# WS2811S.net
KiCad netlist of a schematic drawn in Altium Designer
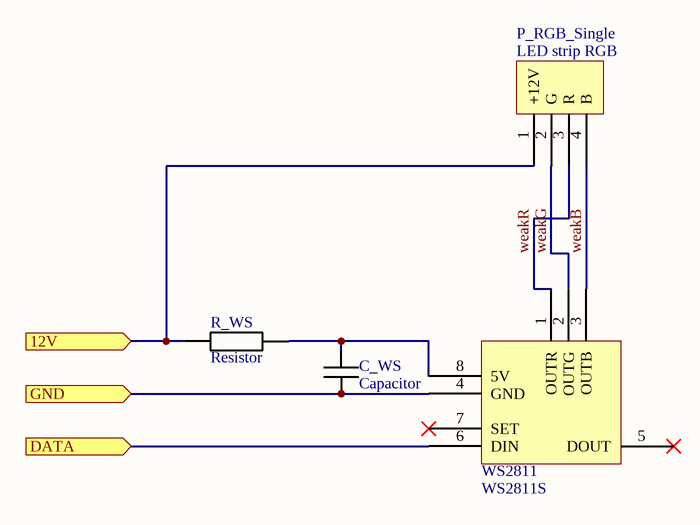
[diagram p0: WS2811S.SchDoc]

(export (version "E")
  (design (tool "Eeschema 10.0.6"))
  (components
    (comp (ref "C_WS")
      (value "Capacitor")
      (footprint "0805-C")
      (libsource (lib "Core51822-related") (part "Capacitor"))
    )
    (comp (ref "P_RGB_Single")
      (value "LED strip RGB")
      (footprint "LED strip RGB connector")
      (libsource (lib "Core51822-related") (part "LED strip RGB"))
    )
    (comp (ref "R_WS")
      (value "Resistor")
      (footprint "0805-C wide")
      (libsource (lib "Core51822-related") (part "Resistor"))
    )
    (comp (ref "WS2811")
      (value "WS2811S")
      (footprint "SOIC-8")
      (description "RGB LED Controller")
      (libsource (lib "ICs") (part "WS2811S"))
    )
  )
  (nets
    (net (code "1") (name "/12V") (class "Default")
      (node (ref "P_RGB_Single") (pin "1") (pinfunction "+12V_1") (pintype "passive"))
      (node (ref "R_WS") (pin "1") (pinfunction "1_1") (pintype "passive"))
    )
    (net (code "2") (name "/DATA") (class "Default")
      (node (ref "WS2811") (pin "6") (pinfunction "DIN_6") (pintype "passive"))
    )
    (net (code "3") (name "/GND") (class "Default")
      (node (ref "C_WS") (pin "1") (pinfunction "1_1") (pintype "passive"))
      (node (ref "WS2811") (pin "4") (pinfunction "GND_4") (pintype "passive"))
    )
    (net (code "4") (name "/weakB") (class "Default")
      (node (ref "P_RGB_Single") (pin "4") (pinfunction "B_4") (pintype "passive"))
      (node (ref "WS2811") (pin "3") (pinfunction "OUTB_3") (pintype "passive"))
    )
    (net (code "5") (name "/weakG") (class "Default")
      (node (ref "P_RGB_Single") (pin "2") (pinfunction "G_2") (pintype "passive"))
      (node (ref "WS2811") (pin "2") (pinfunction "OUTG_2") (pintype "passive"))
    )
    (net (code "6") (name "/weakR") (class "Default")
      (node (ref "P_RGB_Single") (pin "3") (pinfunction "R_3") (pintype "passive"))
      (node (ref "WS2811") (pin "1") (pinfunction "OUTR_1") (pintype "passive"))
    )
    (net (code "7") (name "Net-(WS2811-5V)") (class "Default")
      (node (ref "C_WS") (pin "2") (pinfunction "2_2") (pintype "passive"))
      (node (ref "R_WS") (pin "2") (pinfunction "2_2") (pintype "passive"))
      (node (ref "WS2811") (pin "8") (pinfunction "5V_8") (pintype "passive"))
    )
    (net (code "8") (name "unconnected-(WS2811-DOUT-Pad5)") (class "Default")
      (node (ref "WS2811") (pin "5") (pinfunction "DOUT_5") (pintype "passive+no_connect"))
    )
    (net (code "9") (name "unconnected-(WS2811-SET-Pad7)") (class "Default")
      (node (ref "WS2811") (pin "7") (pinfunction "SET_7") (pintype "passive+no_connect"))
    )
  )
)
